# shematicEASYEDA.net
KiCad netlist of a schematic drawn in EasyEDA
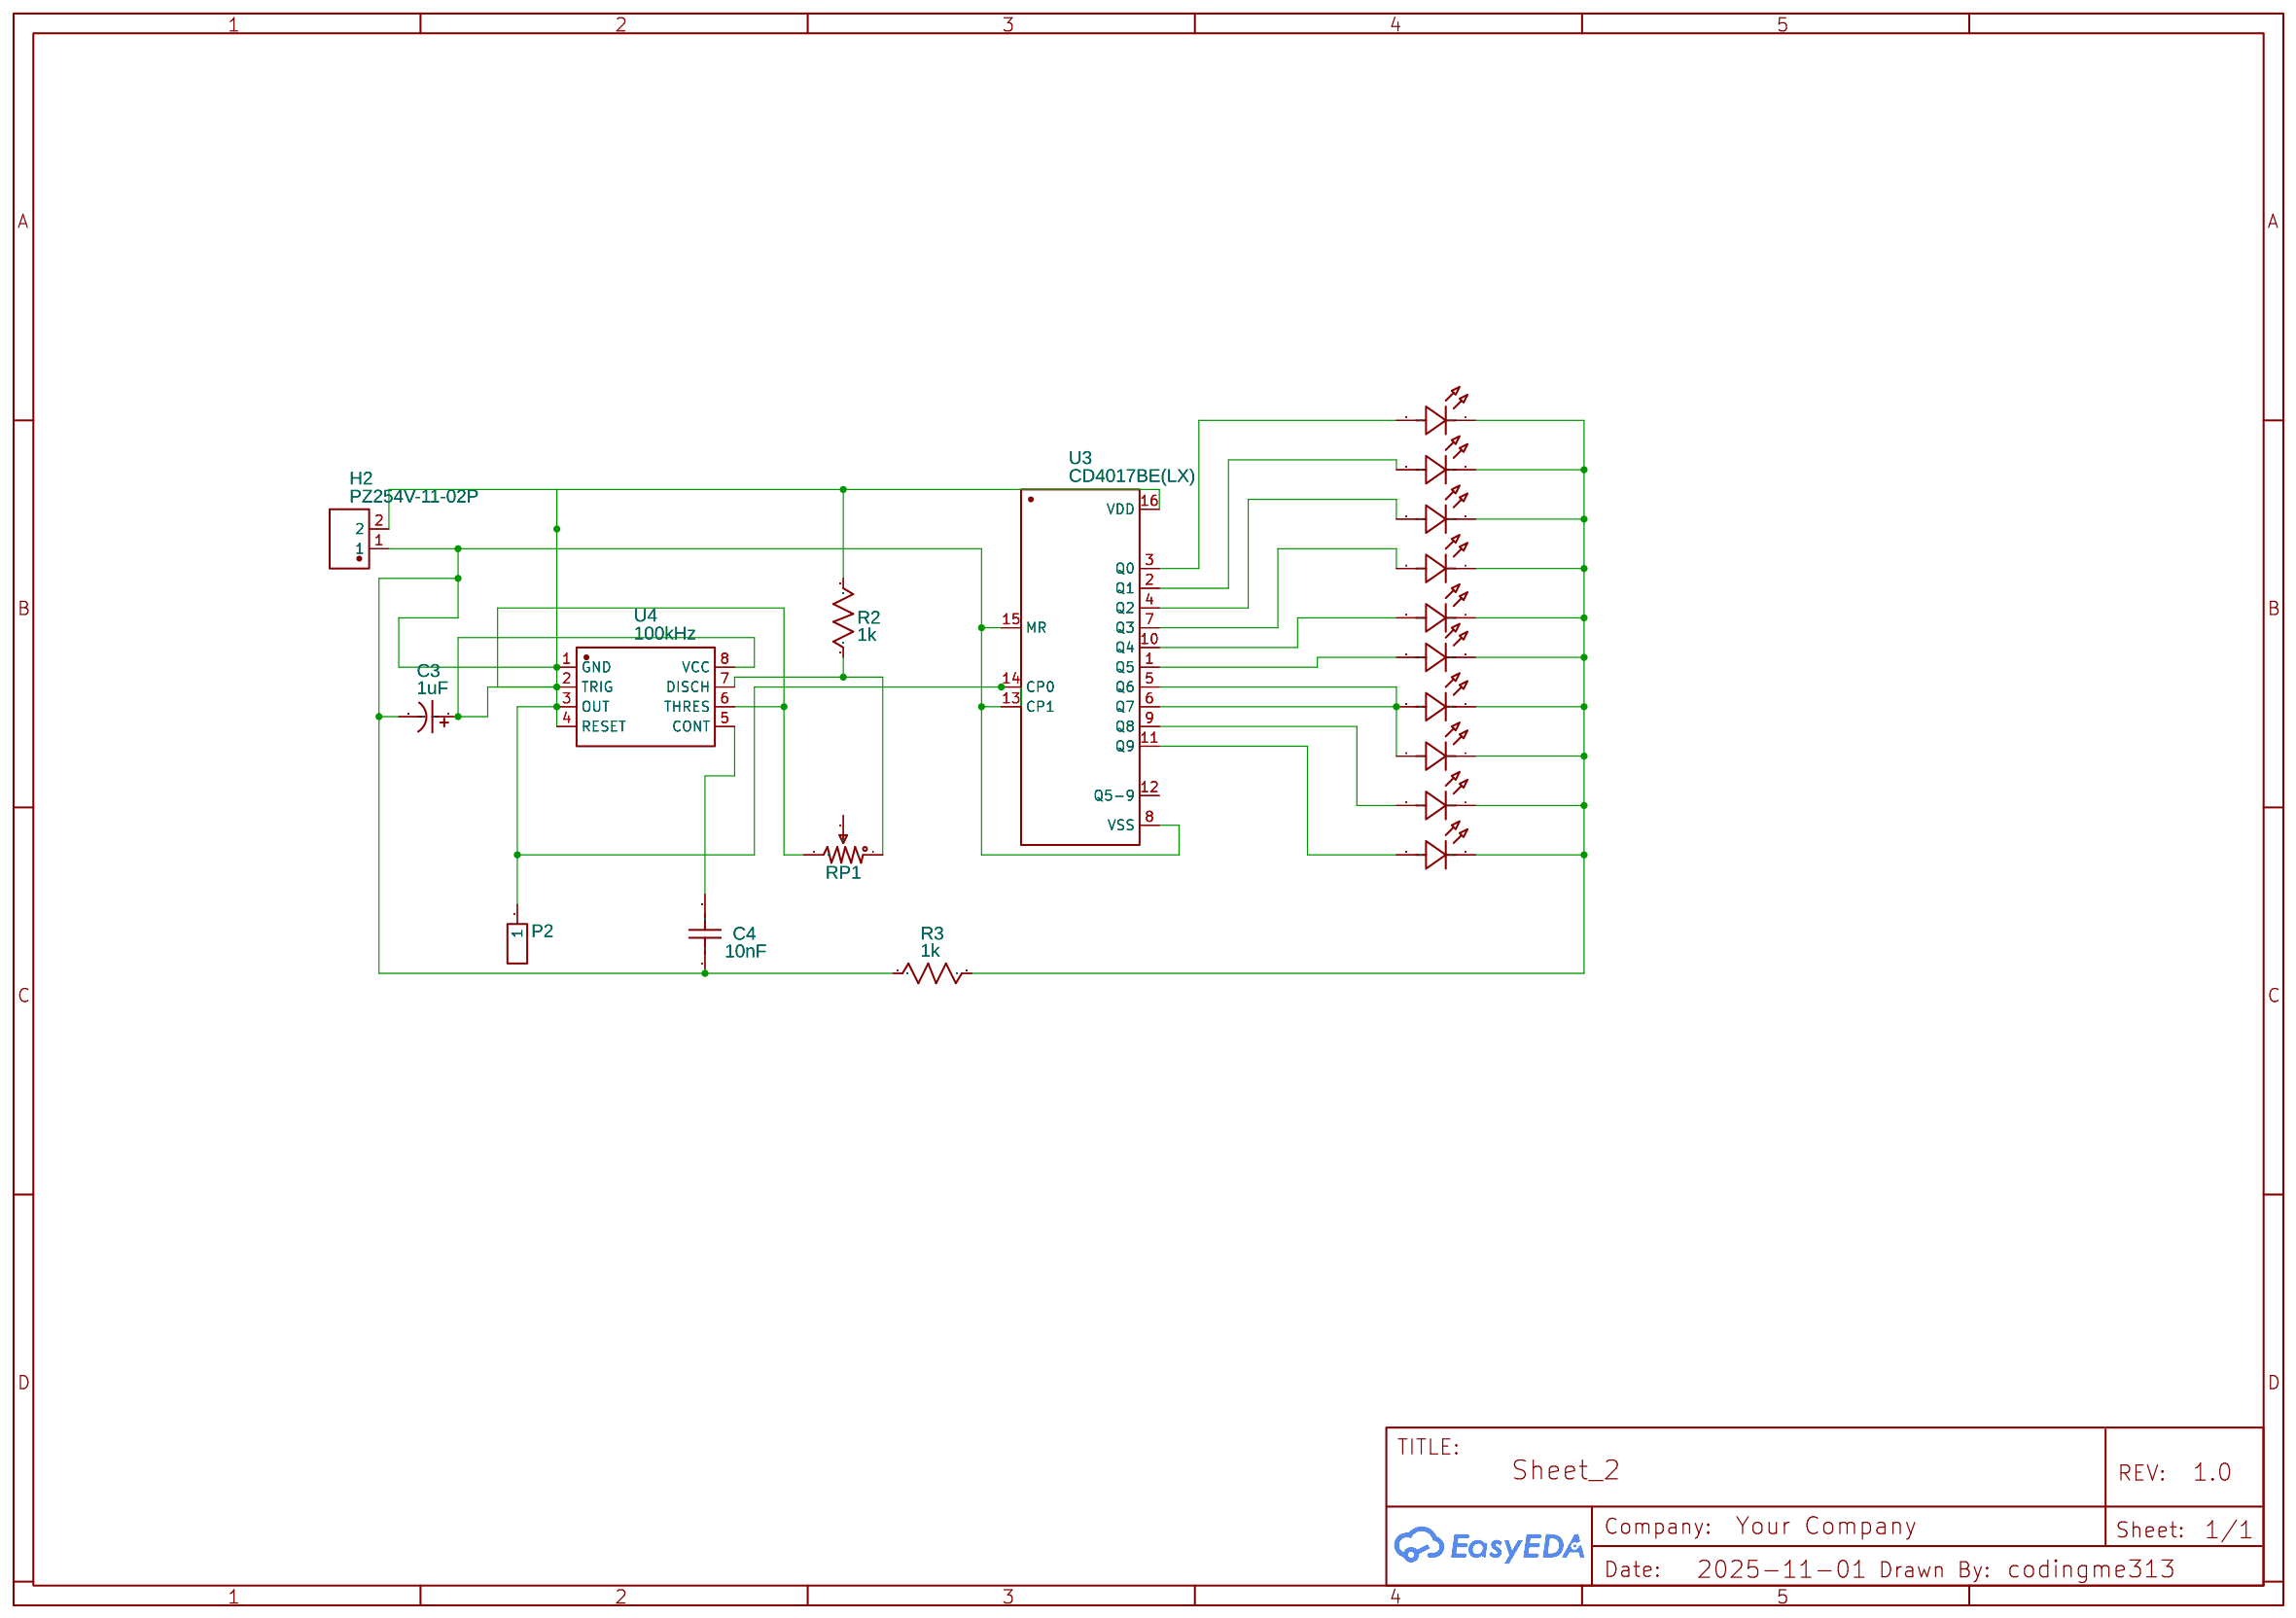
[diagram p0: schematic sheet]

(export (version "E")
  (design (tool "Eeschema 10.0.6"))
  (components
    (comp (ref "C3")
      (value "1uF")
      (fields (field (name "Manufacturer Part") "KF010M050C110A") (field (name "Manufacturer") "CapXon(丰宾)"))
      (libsource (lib "") (part "KF010M050C110A"))
    )
    (comp (ref "C4")
      (value "10nF")
      (fields (field (name "Manufacturer Part") "N09F1B103MN0B0S0N0") (field (name "Manufacturer") "STE(松田)"))
      (libsource (lib "") (part "N09F1B103MN0B0S0N0"))
    )
    (comp (ref "H2")
      (value "PZ254V-11-02P")
      (fields (field (name "Manufacturer") "XFCN(兴飞)"))
      (libsource (lib "") (part "PZ254V-11-02P"))
    )
    (comp (ref "LED1")
      (value "XL-502UWC")
      (fields (field (name "Manufacturer") "XINGLIGHT(成兴光)"))
      (libsource (lib "") (part "XL-502UWC"))
    )
    (comp (ref "LED2")
      (value "XL-502UWC")
      (fields (field (name "Manufacturer") "XINGLIGHT(成兴光)"))
      (libsource (lib "") (part "XL-502UWC"))
    )
    (comp (ref "LED3")
      (value "XL-502UWC")
      (fields (field (name "Manufacturer") "XINGLIGHT(成兴光)"))
      (libsource (lib "") (part "XL-502UWC"))
    )
    (comp (ref "LED4")
      (value "XL-502UWC")
      (fields (field (name "Manufacturer") "XINGLIGHT(成兴光)"))
      (libsource (lib "") (part "XL-502UWC"))
    )
    (comp (ref "LED5")
      (value "XL-502UWC")
      (fields (field (name "Manufacturer") "XINGLIGHT(成兴光)"))
      (libsource (lib "") (part "XL-502UWC"))
    )
    (comp (ref "LED6")
      (value "XL-502UWC")
      (fields (field (name "Manufacturer") "XINGLIGHT(成兴光)"))
      (libsource (lib "") (part "XL-502UWC"))
    )
    (comp (ref "LED7")
      (value "XL-502UWC")
      (fields (field (name "Manufacturer") "XINGLIGHT(成兴光)"))
      (libsource (lib "") (part "XL-502UWC"))
    )
    (comp (ref "LED8")
      (value "XL-502UWC")
      (fields (field (name "Manufacturer") "XINGLIGHT(成兴光)"))
      (libsource (lib "") (part "XL-502UWC"))
    )
    (comp (ref "LED9")
      (value "XL-502UWC")
      (fields (field (name "Manufacturer") "XINGLIGHT(成兴光)"))
      (libsource (lib "") (part "XL-502UWC"))
    )
    (comp (ref "LED12")
      (value "XL-502UWC")
      (fields (field (name "Manufacturer") "XINGLIGHT(成兴光)"))
      (libsource (lib "") (part "XL-502UWC"))
    )
    (comp (ref "P2")
      (value "Header-Male-2.54_1x1")
      (fields (field (name "Manufacturer Part") "2.54-1*1P针") (field (name "Manufacturer") "BOOMELE(博穆精密)"))
      (libsource (lib "") (part "Header-Male-2.54_1x1"))
    )
    (comp (ref "R2") (value "1k") (libsource (lib "") (part "R_0603_US")))
    (comp (ref "R3") (value "1k") (libsource (lib "") (part "R_0603_US_1")))
    (comp (ref "RP1") (value "R_3386P_US") (libsource (lib "") (part "R_3386P_US")))
    (comp (ref "U3")
      (value "CD4017BE(LX)")
      (fields (field (name "Manufacturer") "LX(灵星芯微)"))
      (libsource (lib "") (part "CD4017BE(LX)"))
    )
    (comp (ref "U4")
      (value "100kHz")
      (fields (field (name "Manufacturer Part") "NE555P") (field (name "Manufacturer") "TI(德州仪器)"))
      (libsource (lib "") (part "NE555P"))
    )
  )
  (nets
    (net (code "1") (name "Net-(LED1-A)") (class "Default")
      (node (ref "LED1") (pin "2") (pinfunction "A_2") (pintype "unspecified"))
      (node (ref "U3") (pin "2") (pinfunction "Q1_2") (pintype "unspecified"))
    )
    (net (code "2") (name "Net-(LED1-K)") (class "Default")
      (node (ref "LED1") (pin "1") (pinfunction "K_1") (pintype "unspecified"))
      (node (ref "LED12") (pin "1") (pinfunction "K_1") (pintype "unspecified"))
      (node (ref "LED2") (pin "1") (pinfunction "K_1") (pintype "unspecified"))
      (node (ref "LED3") (pin "1") (pinfunction "K_1") (pintype "unspecified"))
      (node (ref "LED4") (pin "1") (pinfunction "K_1") (pintype "unspecified"))
      (node (ref "LED5") (pin "1") (pinfunction "K_1") (pintype "unspecified"))
      (node (ref "LED6") (pin "1") (pinfunction "K_1") (pintype "unspecified"))
      (node (ref "LED7") (pin "1") (pinfunction "K_1") (pintype "unspecified"))
      (node (ref "LED8") (pin "1") (pinfunction "K_1") (pintype "unspecified"))
      (node (ref "LED9") (pin "1") (pinfunction "K_1") (pintype "unspecified"))
      (node (ref "R3") (pin "1") (pinfunction "1_1") (pintype "unspecified"))
    )
    (net (code "3") (name "Net-(LED2-A)") (class "Default")
      (node (ref "LED2") (pin "2") (pinfunction "A_2") (pintype "unspecified"))
      (node (ref "U3") (pin "4") (pinfunction "Q2_4") (pintype "unspecified"))
    )
    (net (code "4") (name "Net-(LED3-A)") (class "Default")
      (node (ref "LED3") (pin "2") (pinfunction "A_2") (pintype "unspecified"))
      (node (ref "U3") (pin "7") (pinfunction "Q3_7") (pintype "unspecified"))
    )
    (net (code "5") (name "Net-(LED4-A)") (class "Default")
      (node (ref "LED4") (pin "2") (pinfunction "A_2") (pintype "unspecified"))
      (node (ref "U3") (pin "10") (pinfunction "Q4_10") (pintype "unspecified"))
    )
    (net (code "6") (name "Net-(LED5-A)") (class "Default")
      (node (ref "LED5") (pin "2") (pinfunction "A_2") (pintype "unspecified"))
      (node (ref "U3") (pin "1") (pinfunction "Q5_1") (pintype "unspecified"))
    )
    (net (code "7") (name "Net-(LED6-A)") (class "Default")
      (node (ref "LED6") (pin "2") (pinfunction "A_2") (pintype "unspecified"))
      (node (ref "LED7") (pin "2") (pinfunction "A_2") (pintype "unspecified"))
      (node (ref "U3") (pin "5") (pinfunction "Q6_5") (pintype "unspecified"))
      (node (ref "U3") (pin "6") (pinfunction "Q7_6") (pintype "unspecified"))
    )
    (net (code "8") (name "Net-(LED8-A)") (class "Default")
      (node (ref "LED8") (pin "2") (pinfunction "A_2") (pintype "unspecified"))
      (node (ref "U3") (pin "9") (pinfunction "Q8_9") (pintype "unspecified"))
    )
    (net (code "9") (name "Net-(LED9-A)") (class "Default")
      (node (ref "LED9") (pin "2") (pinfunction "A_2") (pintype "unspecified"))
      (node (ref "U3") (pin "11") (pinfunction "Q9_11") (pintype "unspecified"))
    )
    (net (code "10") (name "Net-(LED12-A)") (class "Default")
      (node (ref "LED12") (pin "2") (pinfunction "A_2") (pintype "unspecified"))
      (node (ref "U3") (pin "3") (pinfunction "Q0_3") (pintype "unspecified"))
    )
    (net (code "11") (name "Net-(U3-CP0)") (class "Default")
      (node (ref "C3") (pin "1") (pinfunction "1_1") (pintype "input"))
      (node (ref "C3") (pin "2") (pinfunction "2_2") (pintype "input"))
      (node (ref "C4") (pin "1") (pinfunction "1_1") (pintype "unspecified"))
      (node (ref "H2") (pin "1") (pinfunction "1_1") (pintype "unspecified"))
      (node (ref "H2") (pin "2") (pinfunction "2_2") (pintype "unspecified"))
      (node (ref "P2") (pin "1") (pinfunction "1_1") (pintype "input"))
      (node (ref "R2") (pin "2") (pinfunction "2_2") (pintype "unspecified"))
      (node (ref "R3") (pin "2") (pinfunction "2_2") (pintype "unspecified"))
      (node (ref "RP1") (pin "3") (pinfunction "3_3") (pintype "unspecified"))
      (node (ref "U3") (pin "13") (pinfunction "CP1_13") (pintype "unspecified"))
      (node (ref "U3") (pin "14") (pinfunction "CP0_14") (pintype "unspecified"))
      (node (ref "U3") (pin "15") (pinfunction "MR_15") (pintype "unspecified"))
      (node (ref "U3") (pin "16") (pinfunction "VDD_16") (pintype "unspecified"))
      (node (ref "U3") (pin "8") (pinfunction "VSS_8") (pintype "unspecified"))
      (node (ref "U4") (pin "1") (pinfunction "GND_1") (pintype "unspecified"))
      (node (ref "U4") (pin "2") (pinfunction "TRIG_2") (pintype "unspecified"))
      (node (ref "U4") (pin "3") (pinfunction "OUT_3") (pintype "unspecified"))
      (node (ref "U4") (pin "4") (pinfunction "RESET_4") (pintype "unspecified"))
      (node (ref "U4") (pin "6") (pinfunction "THRES_6") (pintype "unspecified"))
      (node (ref "U4") (pin "8") (pinfunction "VCC_8") (pintype "unspecified"))
    )
    (net (code "12") (name "Net-(U4-CONT)") (class "Default")
      (node (ref "C4") (pin "2") (pinfunction "2_2") (pintype "unspecified"))
      (node (ref "U4") (pin "5") (pinfunction "CONT_5") (pintype "unspecified"))
    )
    (net (code "13") (name "Net-(U4-DISCH)") (class "Default")
      (node (ref "R2") (pin "1") (pinfunction "1_1") (pintype "unspecified"))
      (node (ref "RP1") (pin "1") (pinfunction "1_1") (pintype "unspecified"))
      (node (ref "U4") (pin "7") (pinfunction "DISCH_7") (pintype "unspecified"))
    )
    (net (code "14") (name "unconnected-(RP1-Pad2)") (class "Default")
      (node (ref "RP1") (pin "2") (pinfunction "2_2") (pintype "unspecified"))
    )
    (net (code "15") (name "unconnected-(U3-Q5-9-Pad12)") (class "Default")
      (node (ref "U3") (pin "12") (pinfunction "Q5-9_12") (pintype "unspecified"))
    )
  )
)
